# PCB_PDB.net
KiCad netlist of a schematic drawn in Altium Designer
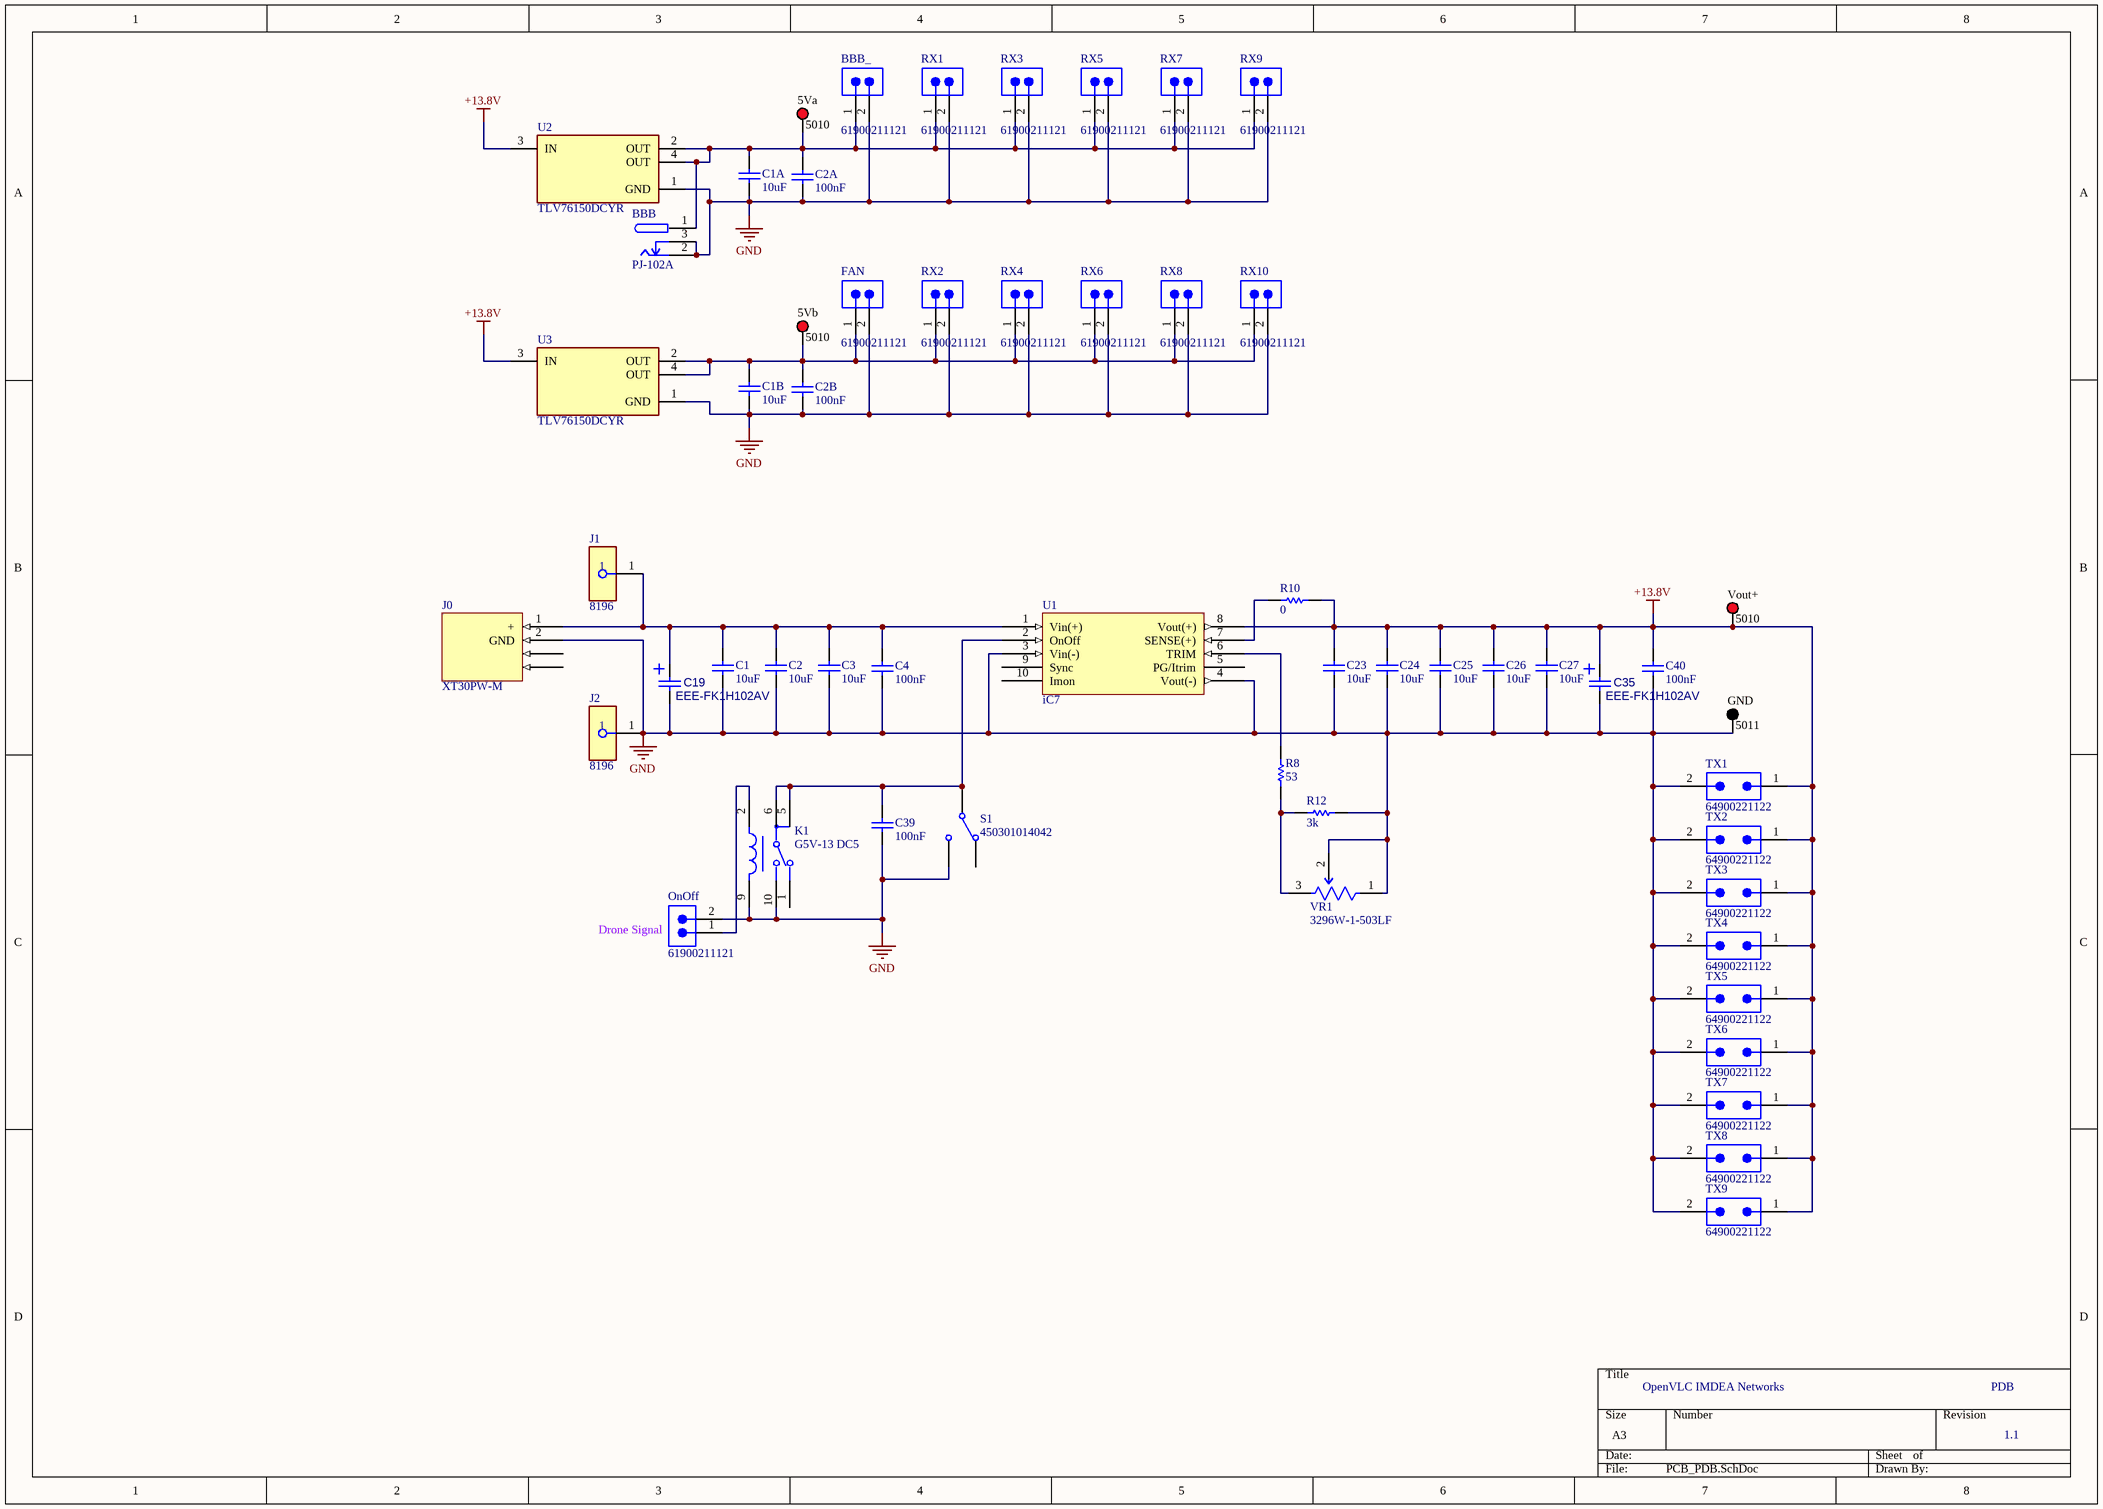
[diagram p0: PCB_PDB.SchDoc]

(export (version "E")
  (design (tool "Eeschema 10.0.6"))
  (components
    (comp (ref "5Va")
      (value "5010")
      (footprint "KSTN-5010_V")
      (description "Test Point, Red, Through Hole, RoHS, Bulk")
      (fields (field (name "MANUFACTURER") "Keystone"))
      (libsource (lib "Altium Content Vault") (part "TESTPOINT_RED"))
    )
    (comp (ref "5Vb")
      (value "5010")
      (footprint "KSTN-5010_V")
      (description "Test Point, Red, Through Hole, RoHS, Bulk")
      (fields (field (name "MANUFACTURER") "Keystone"))
      (libsource (lib "Altium Content Vault") (part "TESTPOINT_RED"))
    )
    (comp (ref "BBB")
      (value "PJ-102A")
      (footprint "FP-PJ-102A-MFG")
      (description "PJ-102A 2.0 x 6.5 mm, 2.5 A, Horizontal, Through Hole, Tapered Pins, Dc Power Jack Connector")
      (libsource (lib "Altium Content Vault") (part "c639f672d24b5d70918fa8d934b95d1"))
    )
    (comp (ref "BBB_")
      (value "61900211121")
      (footprint "61900211121")
      (libsource (lib "Altium Content Vault") (part "Header_Male_1R_02P"))
    )
    (comp (ref "C1")
      (value "10uF")
      (footprint "RESC1608X55N")
      (description "Capacitor")
      (fields (field (name "Comment") "GRM188R6YA106MA73D") (field (name "PUBLISHER") "Altium Limited"))
      (libsource (lib "Miscellaneous Devices") (part "Cap"))
    )
    (comp (ref "C1A")
      (value "10uF")
      (footprint "RESC1608X55N")
      (description "Capacitor")
      (fields (field (name "Comment") "GRM188R6YA106MA73D") (field (name "PUBLISHER") "Altium Limited"))
      (libsource (lib "Miscellaneous Devices") (part "Cap"))
    )
    (comp (ref "C1B")
      (value "10uF")
      (footprint "RESC1608X55N")
      (description "Capacitor")
      (fields (field (name "Comment") "GRM188R6YA106MA73D") (field (name "PUBLISHER") "Altium Limited"))
      (libsource (lib "Miscellaneous Devices") (part "Cap"))
    )
    (comp (ref "C2")
      (value "10uF")
      (footprint "RESC1608X55N")
      (description "Capacitor")
      (fields (field (name "Comment") "GRM188R6YA106MA73D") (field (name "PUBLISHER") "Altium Limited"))
      (libsource (lib "Miscellaneous Devices") (part "Cap"))
    )
    (comp (ref "C2A")
      (value "100nF")
      (footprint "RESC1608X55N")
      (description "Capacitor")
      (fields (field (name "Comment") "GCM188R71H104KA57J") (field (name "PUBLISHER") "Altium Limited"))
      (libsource (lib "Miscellaneous Devices") (part "Cap"))
    )
    (comp (ref "C2B")
      (value "100nF")
      (footprint "RESC1608X55N")
      (description "Capacitor")
      (fields (field (name "Comment") "GCM188R71H104KA57J") (field (name "PUBLISHER") "Altium Limited"))
      (libsource (lib "Miscellaneous Devices") (part "Cap"))
    )
    (comp (ref "C3")
      (value "10uF")
      (footprint "RESC1608X55N")
      (description "Capacitor")
      (fields (field (name "Comment") "GRM188R6YA106MA73D") (field (name "PUBLISHER") "Altium Limited"))
      (libsource (lib "Miscellaneous Devices") (part "Cap"))
    )
    (comp (ref "C4")
      (value "100nF")
      (footprint "RESC1608X55N")
      (description "Capacitor")
      (fields (field (name "Comment") "GCM188R71H104KA57J") (field (name "PUBLISHER") "Altium Limited"))
      (libsource (lib "Miscellaneous Devices") (part "Cap"))
    )
    (comp (ref "C19")
      (value "EEE-FK1H102AV")
      (footprint "CAP-17x17")
      (description "CAP-17x17")
      (libsource (lib "Edson Santos") (part "CAP-17x17"))
    )
    (comp (ref "C23")
      (value "10uF")
      (footprint "RESC1608X55N")
      (description "Capacitor")
      (fields (field (name "Comment") "GRM188R6YA106MA73D") (field (name "PUBLISHER") "Altium Limited"))
      (libsource (lib "Miscellaneous Devices") (part "Cap"))
    )
    (comp (ref "C24")
      (value "10uF")
      (footprint "RESC1608X55N")
      (description "Capacitor")
      (fields (field (name "Comment") "GRM188R6YA106MA73D") (field (name "PUBLISHER") "Altium Limited"))
      (libsource (lib "Miscellaneous Devices") (part "Cap"))
    )
    (comp (ref "C25")
      (value "10uF")
      (footprint "RESC1608X55N")
      (description "Capacitor")
      (fields (field (name "Comment") "GRM188R6YA106MA73D") (field (name "PUBLISHER") "Altium Limited"))
      (libsource (lib "Miscellaneous Devices") (part "Cap"))
    )
    (comp (ref "C26")
      (value "10uF")
      (footprint "RESC1608X55N")
      (description "Capacitor")
      (fields (field (name "Comment") "GRM188R6YA106MA73D") (field (name "PUBLISHER") "Altium Limited"))
      (libsource (lib "Miscellaneous Devices") (part "Cap"))
    )
    (comp (ref "C27")
      (value "10uF")
      (footprint "RESC1608X55N")
      (description "Capacitor")
      (fields (field (name "Comment") "GRM188R6YA106MA73D") (field (name "PUBLISHER") "Altium Limited"))
      (libsource (lib "Miscellaneous Devices") (part "Cap"))
    )
    (comp (ref "C35")
      (value "EEE-FK1H102AV")
      (footprint "CAP-17x17")
      (description "CAP-17x17")
      (libsource (lib "Edson Santos") (part "CAP-17x17"))
    )
    (comp (ref "C39")
      (value "100nF")
      (footprint "RESC1608X55N")
      (description "Capacitor")
      (fields (field (name "Comment") "GCM188R71H104KA57J") (field (name "PUBLISHER") "Altium Limited"))
      (libsource (lib "Miscellaneous Devices") (part "Cap"))
    )
    (comp (ref "C40")
      (value "100nF")
      (footprint "RESC1608X55N")
      (description "Capacitor")
      (fields (field (name "Comment") "GCM188R71H104KA57J") (field (name "PUBLISHER") "Altium Limited"))
      (libsource (lib "Miscellaneous Devices") (part "Cap"))
    )
    (comp (ref "FAN")
      (value "61900211121")
      (footprint "61900211121")
      (libsource (lib "Altium Content Vault") (part "Header_Male_1R_02P"))
    )
    (comp (ref "GND")
      (value "5011")
      (footprint "KSTN-5011_V")
      (description "Test Point, Black, Through Hole, RoHS, Bulk")
      (fields (field (name "MANUFACTURER") "Keystone"))
      (libsource (lib "Altium Content Vault") (part "TESTPOINT_BLACK"))
    )
    (comp (ref "J0")
      (value "XT30PW-M")
      (footprint "XT30-Footprint-1")
      (libsource (lib "Edson Santos") (part "XT30PW-M"))
    )
    (comp (ref "J1")
      (value "8196")
      (footprint "FP-8196-MFG")
      (description "8196 PC Screw Terminal 0.67 in. L Brass Tin Plate Stainless Steel Mounting Hole 0.045 in. T")
      (libsource (lib "Altium Content Vault") (part "98815daf2f2c152b0c43f5ab9800df6"))
    )
    (comp (ref "J2")
      (value "8196")
      (footprint "FP-8196-MFG")
      (description "8196 PC Screw Terminal 0.67 in. L Brass Tin Plate Stainless Steel Mounting Hole 0.045 in. T")
      (libsource (lib "Altium Content Vault") (part "98815daf2f2c152b0c43f5ab9800df6"))
    )
    (comp (ref "K1")
      (value "G5V-13 DC5")
      (footprint "FP-G5V-13_DC5-MFG")
      (description "RELAY GEN PURPOSE SPDT 1A 5VDC")
      (libsource (lib "Altium Content Vault") (part "f0f19af8d64f0b7d991e63e7b06891a"))
    )
    (comp (ref "OnOff")
      (value "61900211121")
      (footprint "61900211121")
      (libsource (lib "Altium Content Vault") (part "Header_Male_1R_02P"))
    )
    (comp (ref "R8")
      (value "53")
      (footprint "RESC1608X55N")
      (description "Resistor")
      (fields (field (name "Comment") "RN73R1JTTD53R0B25") (field (name "PUBLISHER") "Altium Limited"))
      (libsource (lib "Miscellaneous Devices") (part "Res1"))
    )
    (comp (ref "R10")
      (value "0")
      (footprint "RESC1608X55N")
      (description "Resistor")
      (fields (field (name "Comment") "RMCF0603ZT0R00") (field (name "PUBLISHER") "Altium Limited"))
      (libsource (lib "Miscellaneous Devices") (part "Res1"))
    )
    (comp (ref "R12")
      (value "3k")
      (footprint "RESC1608X55N")
      (description "Resistor")
      (fields (field (name "Comment") "RK73H1JTTD2001D") (field (name "PUBLISHER") "Altium Limited"))
      (libsource (lib "Miscellaneous Devices") (part "Res1"))
    )
    (comp (ref "RX1")
      (value "61900211121")
      (footprint "61900211121")
      (libsource (lib "Altium Content Vault") (part "Header_Male_1R_02P"))
    )
    (comp (ref "RX2")
      (value "61900211121")
      (footprint "61900211121")
      (libsource (lib "Altium Content Vault") (part "Header_Male_1R_02P"))
    )
    (comp (ref "RX3")
      (value "61900211121")
      (footprint "61900211121")
      (libsource (lib "Altium Content Vault") (part "Header_Male_1R_02P"))
    )
    (comp (ref "RX4")
      (value "61900211121")
      (footprint "61900211121")
      (libsource (lib "Altium Content Vault") (part "Header_Male_1R_02P"))
    )
    (comp (ref "RX5")
      (value "61900211121")
      (footprint "61900211121")
      (libsource (lib "Altium Content Vault") (part "Header_Male_1R_02P"))
    )
    (comp (ref "RX6")
      (value "61900211121")
      (footprint "61900211121")
      (libsource (lib "Altium Content Vault") (part "Header_Male_1R_02P"))
    )
    (comp (ref "RX7")
      (value "61900211121")
      (footprint "61900211121")
      (libsource (lib "Altium Content Vault") (part "Header_Male_1R_02P"))
    )
    (comp (ref "RX8")
      (value "61900211121")
      (footprint "61900211121")
      (libsource (lib "Altium Content Vault") (part "Header_Male_1R_02P"))
    )
    (comp (ref "RX9")
      (value "61900211121")
      (footprint "61900211121")
      (libsource (lib "Altium Content Vault") (part "Header_Male_1R_02P"))
    )
    (comp (ref "RX10")
      (value "61900211121")
      (footprint "61900211121")
      (libsource (lib "Altium Content Vault") (part "Header_Male_1R_02P"))
    )
    (comp (ref "S1")
      (value "450301014042")
      (footprint "450301014042")
      (libsource (lib "Altium Content Vault") (part "SPDT"))
    )
    (comp (ref "TX1")
      (value "64900221122")
      (footprint "64900221122")
      (libsource (lib "Altium Content Vault") (part "Header_Male_2R_02P(A)"))
    )
    (comp (ref "TX2")
      (value "64900221122")
      (footprint "64900221122")
      (libsource (lib "Altium Content Vault") (part "Header_Male_2R_02P(A)"))
    )
    (comp (ref "TX3")
      (value "64900221122")
      (footprint "64900221122")
      (libsource (lib "Altium Content Vault") (part "Header_Male_2R_02P(A)"))
    )
    (comp (ref "TX4")
      (value "64900221122")
      (footprint "64900221122")
      (libsource (lib "Altium Content Vault") (part "Header_Male_2R_02P(A)"))
    )
    (comp (ref "TX5")
      (value "64900221122")
      (footprint "64900221122")
      (libsource (lib "Altium Content Vault") (part "Header_Male_2R_02P(A)"))
    )
    (comp (ref "TX6")
      (value "64900221122")
      (footprint "64900221122")
      (libsource (lib "Altium Content Vault") (part "Header_Male_2R_02P(A)"))
    )
    (comp (ref "TX7")
      (value "64900221122")
      (footprint "64900221122")
      (libsource (lib "Altium Content Vault") (part "Header_Male_2R_02P(A)"))
    )
    (comp (ref "TX8")
      (value "64900221122")
      (footprint "64900221122")
      (libsource (lib "Altium Content Vault") (part "Header_Male_2R_02P(A)"))
    )
    (comp (ref "TX9")
      (value "64900221122")
      (footprint "64900221122")
      (libsource (lib "Altium Content Vault") (part "Header_Male_2R_02P(A)"))
    )
    (comp (ref "U1")
      (value "iC7")
      (footprint "New footprint 1")
      (libsource (lib "Edson Santos") (part "i7C"))
    )
    (comp (ref "U2")
      (value "TLV76150DCYR")
      (footprint "FP-DCY0004A-MFG")
      (description "TLV76150DCYR 1-A 16-V high-PSRR linear voltage regulator 4-SOT-223 -40 to 125")
      (libsource (lib "Altium Content Vault") (part "991ffb903c51cf6179ce9942c0606aa"))
    )
    (comp (ref "U3")
      (value "TLV76150DCYR")
      (footprint "FP-DCY0004A-MFG")
      (description "TLV76150DCYR 1-A 16-V high-PSRR linear voltage regulator 4-SOT-223 -40 to 125")
      (libsource (lib "Altium Content Vault") (part "991ffb903c51cf6179ce9942c0606aa"))
    )
    (comp (ref "Vout+")
      (value "5010")
      (footprint "KSTN-5010_V")
      (description "Test Point, Red, Through Hole, RoHS, Bulk")
      (fields (field (name "MANUFACTURER") "Keystone"))
      (libsource (lib "Altium Content Vault") (part "TESTPOINT_RED"))
    )
    (comp (ref "VR1")
      (value "3296W-1-503LF")
      (footprint "FP-3296W-MFG")
      (description "TRIMMER 50K OHM 0.5W PC PIN TOP")
      (fields (field (name "TOLERANCE") "10%"))
      (libsource (lib "Altium Content Vault") (part "2dcfd2547301a7d3209a5e99acfd772"))
    )
  )
  (nets
    (net (code "1") (name "+13.8V") (class "Default")
      (node (ref "C23") (pin "2") (pinfunction "2_2") (pintype "passive"))
      (node (ref "C24") (pin "2") (pinfunction "2_2") (pintype "passive"))
      (node (ref "C25") (pin "2") (pinfunction "2_2") (pintype "passive"))
      (node (ref "C26") (pin "2") (pinfunction "2_2") (pintype "passive"))
      (node (ref "C27") (pin "2") (pinfunction "2_2") (pintype "passive"))
      (node (ref "C35") (pin "1") (pinfunction "1_1") (pintype "passive"))
      (node (ref "C40") (pin "2") (pinfunction "2_2") (pintype "passive"))
      (node (ref "R10") (pin "1") (pinfunction "1_1") (pintype "passive"))
      (node (ref "TX1") (pin "1") (pinfunction "1_1") (pintype "passive"))
      (node (ref "TX2") (pin "1") (pinfunction "1_1") (pintype "passive"))
      (node (ref "TX3") (pin "1") (pinfunction "1_1") (pintype "passive"))
      (node (ref "TX4") (pin "1") (pinfunction "1_1") (pintype "passive"))
      (node (ref "TX5") (pin "1") (pinfunction "1_1") (pintype "passive"))
      (node (ref "TX6") (pin "1") (pinfunction "1_1") (pintype "passive"))
      (node (ref "TX7") (pin "1") (pinfunction "1_1") (pintype "passive"))
      (node (ref "TX8") (pin "1") (pinfunction "1_1") (pintype "passive"))
      (node (ref "TX9") (pin "1") (pinfunction "1_1") (pintype "passive"))
      (node (ref "U1") (pin "8") (pinfunction "Vout(+)_8") (pintype "output"))
      (node (ref "U2") (pin "3") (pinfunction "IN_3") (pintype "power_in"))
      (node (ref "U3") (pin "3") (pinfunction "IN_3") (pintype "power_in"))
      (node (ref "Vout+") (pin "1") (pinfunction "1_1") (pintype "passive"))
    )
    (net (code "2") (name "GND") (class "Default")
      (node (ref "BBB") (pin "2") (pinfunction "2_2") (pintype "passive"))
      (node (ref "BBB") (pin "3") (pinfunction "3_3") (pintype "passive"))
      (node (ref "BBB_") (pin "2") (pinfunction "2_2") (pintype "passive"))
      (node (ref "C1") (pin "1") (pinfunction "1_1") (pintype "passive"))
      (node (ref "C19") (pin "2") (pinfunction "2_2") (pintype "passive"))
      (node (ref "C1A") (pin "1") (pinfunction "1_1") (pintype "passive"))
      (node (ref "C1B") (pin "1") (pinfunction "1_1") (pintype "passive"))
      (node (ref "C2") (pin "1") (pinfunction "1_1") (pintype "passive"))
      (node (ref "C23") (pin "1") (pinfunction "1_1") (pintype "passive"))
      (node (ref "C24") (pin "1") (pinfunction "1_1") (pintype "passive"))
      (node (ref "C25") (pin "1") (pinfunction "1_1") (pintype "passive"))
      (node (ref "C26") (pin "1") (pinfunction "1_1") (pintype "passive"))
      (node (ref "C27") (pin "1") (pinfunction "1_1") (pintype "passive"))
      (node (ref "C2A") (pin "2") (pinfunction "2_2") (pintype "passive"))
      (node (ref "C2B") (pin "2") (pinfunction "2_2") (pintype "passive"))
      (node (ref "C3") (pin "1") (pinfunction "1_1") (pintype "passive"))
      (node (ref "C35") (pin "2") (pinfunction "2_2") (pintype "passive"))
      (node (ref "C39") (pin "2") (pinfunction "2_2") (pintype "passive"))
      (node (ref "C4") (pin "2") (pinfunction "2_2") (pintype "passive"))
      (node (ref "C40") (pin "1") (pinfunction "1_1") (pintype "passive"))
      (node (ref "FAN") (pin "2") (pinfunction "2_2") (pintype "passive"))
      (node (ref "GND") (pin "1") (pinfunction "1_1") (pintype "passive"))
      (node (ref "J0") (pin "2") (pinfunction "GND_2") (pintype "input"))
      (node (ref "J2") (pin "1") (pinfunction "1_1") (pintype "passive"))
      (node (ref "K1") (pin "10") (pinfunction "10_10") (pintype "passive"))
      (node (ref "K1") (pin "9") (pinfunction "9_9") (pintype "passive"))
      (node (ref "OnOff") (pin "2") (pinfunction "2_2") (pintype "passive"))
      (node (ref "R12") (pin "1") (pinfunction "1_1") (pintype "passive"))
      (node (ref "RX1") (pin "2") (pinfunction "2_2") (pintype "passive"))
      (node (ref "RX10") (pin "2") (pinfunction "2_2") (pintype "passive"))
      (node (ref "RX2") (pin "2") (pinfunction "2_2") (pintype "passive"))
      (node (ref "RX3") (pin "2") (pinfunction "2_2") (pintype "passive"))
      (node (ref "RX4") (pin "2") (pinfunction "2_2") (pintype "passive"))
      (node (ref "RX5") (pin "2") (pinfunction "2_2") (pintype "passive"))
      (node (ref "RX6") (pin "2") (pinfunction "2_2") (pintype "passive"))
      (node (ref "RX7") (pin "2") (pinfunction "2_2") (pintype "passive"))
      (node (ref "RX8") (pin "2") (pinfunction "2_2") (pintype "passive"))
      (node (ref "RX9") (pin "2") (pinfunction "2_2") (pintype "passive"))
      (node (ref "S1") (pin "L2") (pinfunction "L2_L2") (pintype "passive"))
      (node (ref "TX1") (pin "2") (pinfunction "2_2") (pintype "passive"))
      (node (ref "TX2") (pin "2") (pinfunction "2_2") (pintype "passive"))
      (node (ref "TX3") (pin "2") (pinfunction "2_2") (pintype "passive"))
      (node (ref "TX4") (pin "2") (pinfunction "2_2") (pintype "passive"))
      (node (ref "TX5") (pin "2") (pinfunction "2_2") (pintype "passive"))
      (node (ref "TX6") (pin "2") (pinfunction "2_2") (pintype "passive"))
      (node (ref "TX7") (pin "2") (pinfunction "2_2") (pintype "passive"))
      (node (ref "TX8") (pin "2") (pinfunction "2_2") (pintype "passive"))
      (node (ref "TX9") (pin "2") (pinfunction "2_2") (pintype "passive"))
      (node (ref "U1") (pin "3") (pinfunction "Vin(-)_3") (pintype "input"))
      (node (ref "U1") (pin "4") (pinfunction "Vout(-)_4") (pintype "output"))
      (node (ref "U2") (pin "1") (pinfunction "GND_1") (pintype "power_in"))
      (node (ref "U3") (pin "1") (pinfunction "GND_1") (pintype "power_in"))
      (node (ref "VR1") (pin "1") (pinfunction "CCW_1") (pintype "passive"))
      (node (ref "VR1") (pin "2") (pinfunction "WIPER_2") (pintype "passive"))
    )
    (net (code "3") (name "Net-(5Va-Pad1)") (class "Default")
      (node (ref "5Va") (pin "1") (pinfunction "1_1") (pintype "passive"))
      (node (ref "BBB") (pin "1") (pinfunction "1_1") (pintype "passive"))
      (node (ref "BBB_") (pin "1") (pinfunction "1_1") (pintype "passive"))
      (node (ref "C1A") (pin "2") (pinfunction "2_2") (pintype "passive"))
      (node (ref "C2A") (pin "1") (pinfunction "1_1") (pintype "passive"))
      (node (ref "RX1") (pin "1") (pinfunction "1_1") (pintype "passive"))
      (node (ref "RX3") (pin "1") (pinfunction "1_1") (pintype "passive"))
      (node (ref "RX5") (pin "1") (pinfunction "1_1") (pintype "passive"))
      (node (ref "RX7") (pin "1") (pinfunction "1_1") (pintype "passive"))
      (node (ref "RX9") (pin "1") (pinfunction "1_1") (pintype "passive"))
      (node (ref "U2") (pin "2") (pinfunction "OUT_2") (pintype "passive"))
      (node (ref "U2") (pin "4") (pinfunction "OUT_4") (pintype "passive"))
    )
    (net (code "4") (name "Net-(5Vb-Pad1)") (class "Default")
      (node (ref "5Vb") (pin "1") (pinfunction "1_1") (pintype "passive"))
      (node (ref "C1B") (pin "2") (pinfunction "2_2") (pintype "passive"))
      (node (ref "C2B") (pin "1") (pinfunction "1_1") (pintype "passive"))
      (node (ref "FAN") (pin "1") (pinfunction "1_1") (pintype "passive"))
      (node (ref "RX10") (pin "1") (pinfunction "1_1") (pintype "passive"))
      (node (ref "RX2") (pin "1") (pinfunction "1_1") (pintype "passive"))
      (node (ref "RX4") (pin "1") (pinfunction "1_1") (pintype "passive"))
      (node (ref "RX6") (pin "1") (pinfunction "1_1") (pintype "passive"))
      (node (ref "RX8") (pin "1") (pinfunction "1_1") (pintype "passive"))
      (node (ref "U3") (pin "2") (pinfunction "OUT_2") (pintype "passive"))
      (node (ref "U3") (pin "4") (pinfunction "OUT_4") (pintype "passive"))
    )
    (net (code "5") (name "Net-(J0-+)") (class "Default")
      (node (ref "C1") (pin "2") (pinfunction "2_2") (pintype "passive"))
      (node (ref "C19") (pin "1") (pinfunction "1_1") (pintype "passive"))
      (node (ref "C2") (pin "2") (pinfunction "2_2") (pintype "passive"))
      (node (ref "C3") (pin "2") (pinfunction "2_2") (pintype "passive"))
      (node (ref "C4") (pin "1") (pinfunction "1_1") (pintype "passive"))
      (node (ref "J0") (pin "1") (pinfunction "+_1") (pintype "input"))
      (node (ref "J1") (pin "1") (pinfunction "1_1") (pintype "passive"))
      (node (ref "U1") (pin "1") (pinfunction "Vin(+)_1") (pintype "input"))
    )
    (net (code "6") (name "Net-(K1-Pad2)") (class "Default")
      (node (ref "K1") (pin "2") (pinfunction "2_2") (pintype "passive"))
      (node (ref "OnOff") (pin "1") (pinfunction "1_1") (pintype "passive"))
    )
    (net (code "7") (name "Net-(U1-OnOff)") (class "Default")
      (node (ref "C39") (pin "1") (pinfunction "1_1") (pintype "passive"))
      (node (ref "K1") (pin "5") (pinfunction "5_5") (pintype "passive"))
      (node (ref "K1") (pin "6") (pinfunction "6_6") (pintype "passive"))
      (node (ref "S1") (pin "COM") (pinfunction "COM_COM") (pintype "passive"))
      (node (ref "U1") (pin "2") (pinfunction "OnOff_2") (pintype "input"))
    )
    (net (code "8") (name "Net-(U1-SENSE(+))") (class "Default")
      (node (ref "R10") (pin "2") (pinfunction "2_2") (pintype "passive"))
      (node (ref "U1") (pin "7") (pinfunction "SENSE(+)_7") (pintype "input"))
    )
    (net (code "9") (name "Net-(U1-TRIM)") (class "Default")
      (node (ref "R8") (pin "1") (pinfunction "1_1") (pintype "passive"))
      (node (ref "U1") (pin "6") (pinfunction "TRIM_6") (pintype "input"))
    )
    (net (code "10") (name "Net-(VR1-CW)") (class "Default")
      (node (ref "R12") (pin "2") (pinfunction "2_2") (pintype "passive"))
      (node (ref "R8") (pin "2") (pinfunction "2_2") (pintype "passive"))
      (node (ref "VR1") (pin "3") (pinfunction "CW_3") (pintype "passive"))
    )
    (net (code "11") (name "unconnected-(J0-NC3-Pad3)") (class "Default")
      (node (ref "J0") (pin "3") (pinfunction "NC3_3") (pintype "input"))
    )
    (net (code "12") (name "unconnected-(J0-NC4-Pad4)") (class "Default")
      (node (ref "J0") (pin "4") (pinfunction "NC4_4") (pintype "input"))
    )
    (net (code "13") (name "unconnected-(K1-Pad1)") (class "Default")
      (node (ref "K1") (pin "1") (pinfunction "1_1") (pintype "passive"))
    )
    (net (code "14") (name "unconnected-(S1-PadL1)") (class "Default")
      (node (ref "S1") (pin "L1") (pinfunction "L1_L1") (pintype "passive"))
    )
    (net (code "15") (name "unconnected-(U1-Imon-Pad10)") (class "Default")
      (node (ref "U1") (pin "10") (pinfunction "Imon_10") (pintype "open_collector"))
    )
    (net (code "16") (name "unconnected-(U1-PG{slash}Itrim-Pad5)") (class "Default")
      (node (ref "U1") (pin "5") (pinfunction "PG/Itrim_5") (pintype "open_collector"))
    )
    (net (code "17") (name "unconnected-(U1-Sync-Pad9)") (class "Default")
      (node (ref "U1") (pin "9") (pinfunction "Sync_9") (pintype "open_collector"))
    )
  )
)
